# FPGA.net
KiCad netlist of a schematic drawn in Altium Designer
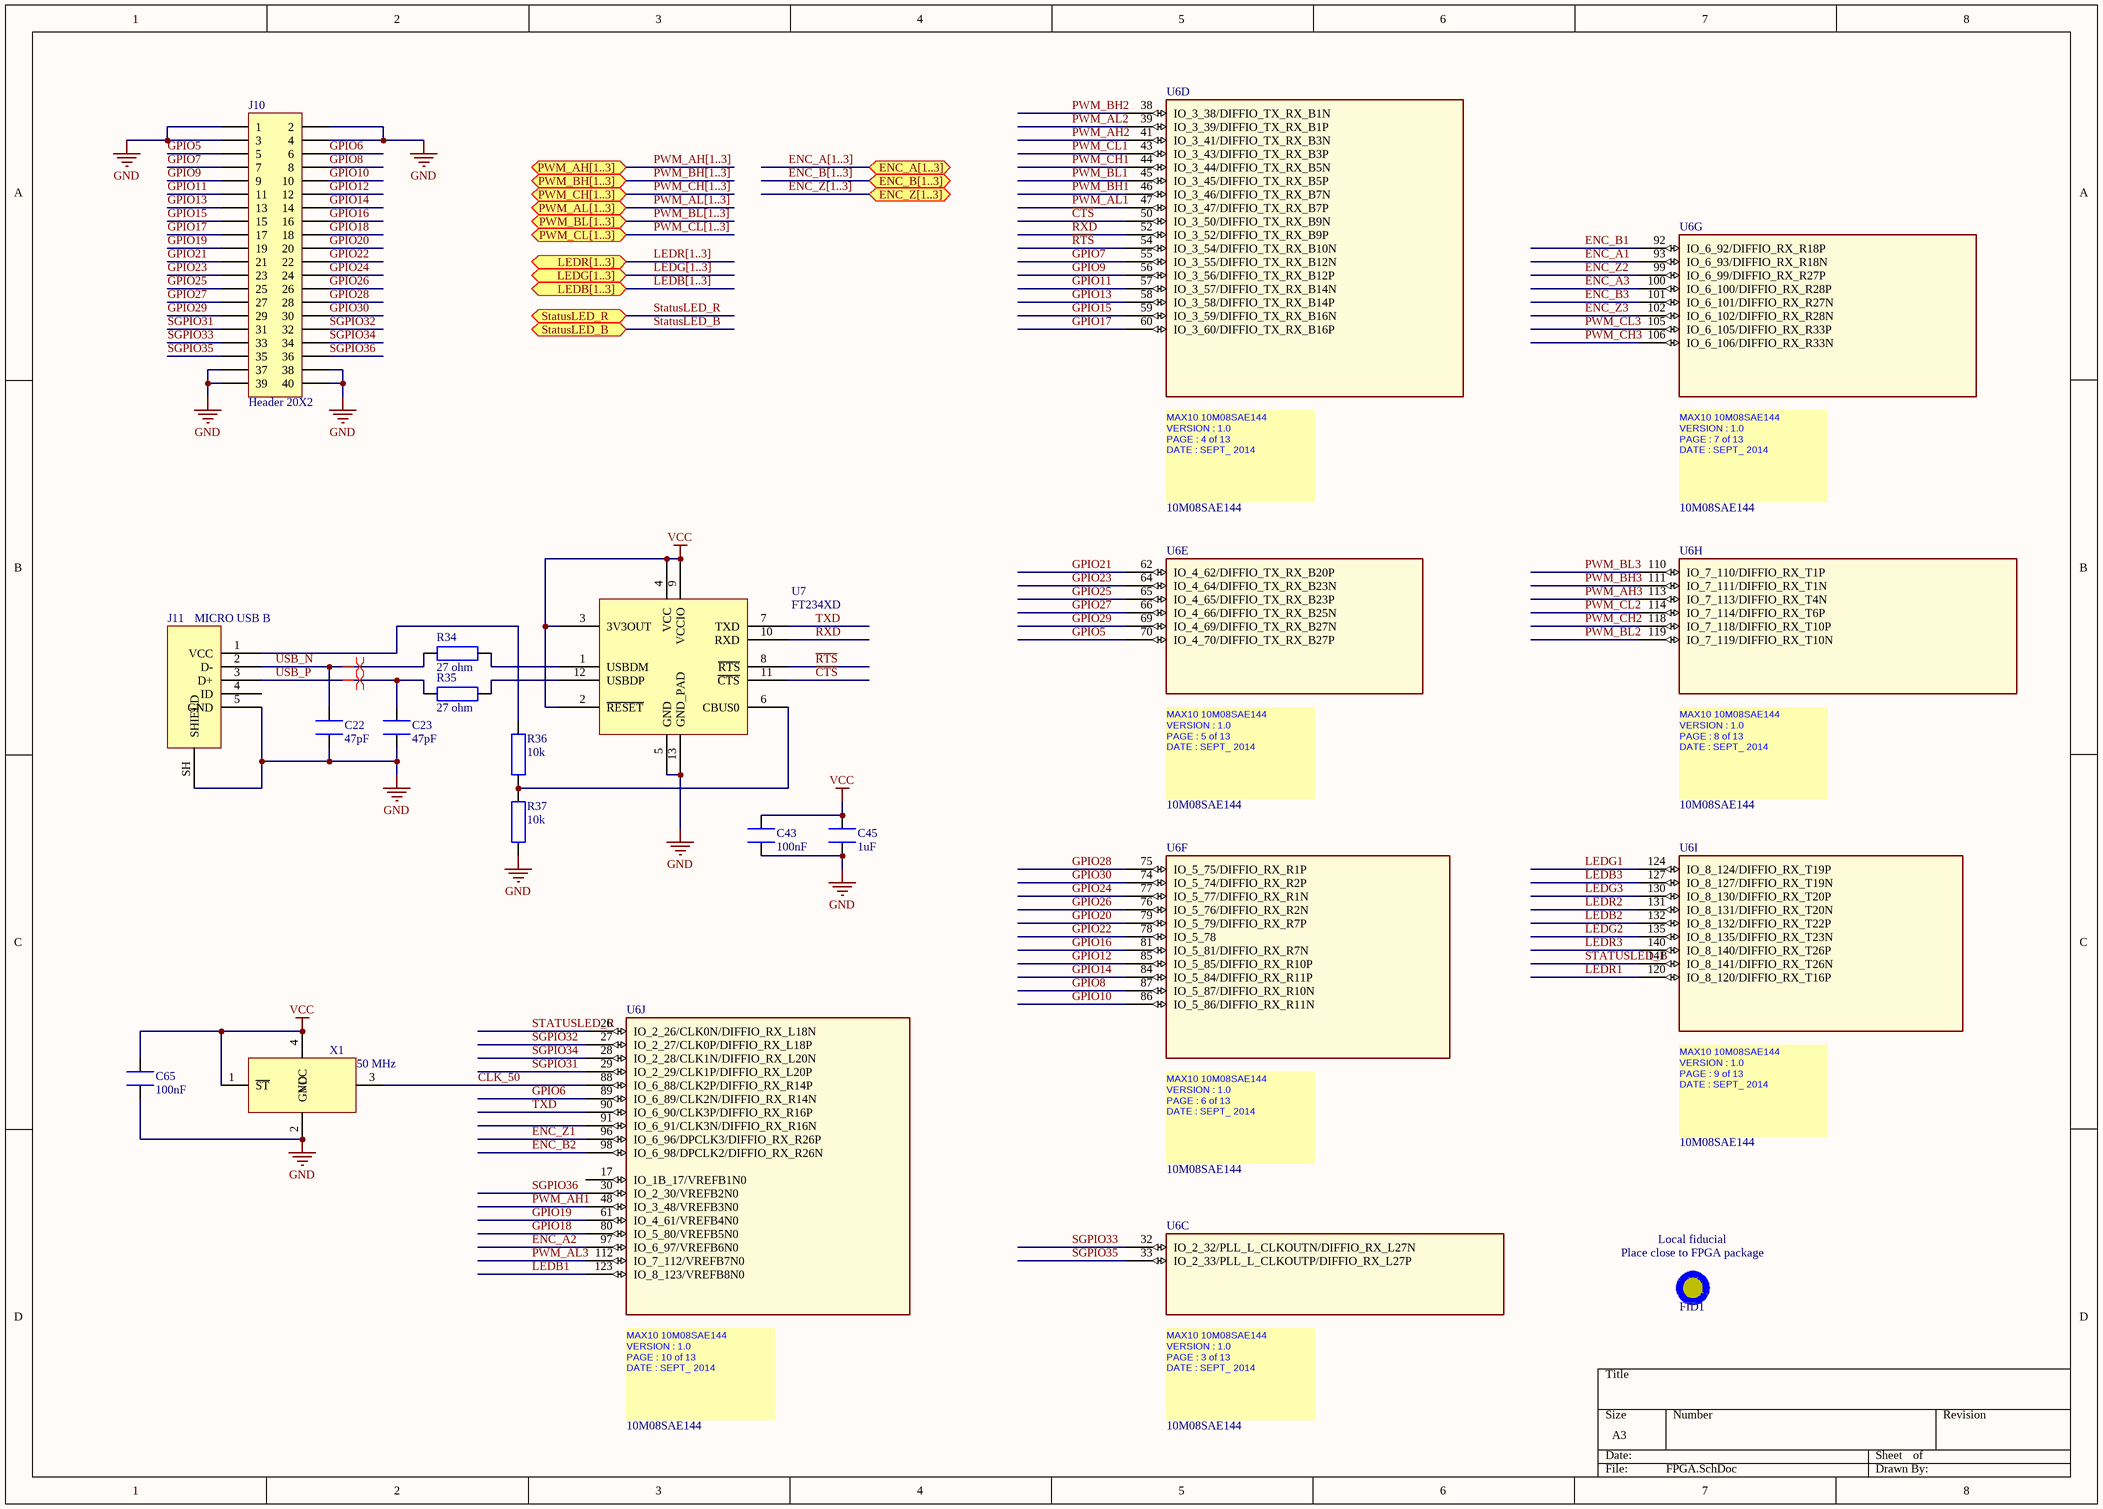
[diagram p0: FPGA.SchDoc]

(export (version "E")
  (design (tool "Eeschema 10.0.6"))
  (components
    (comp (ref "C22")
      (value "47pF")
      (footprint "1608[0603]")
      (description "CAP, MLCC, C0G/NP0, 47PF, 50V, 0603")
      (fields (field (name "Comment") "MC0603N470J500CT"))
      (libsource (lib "CustomComponents") (part "MC0603N470J500CT"))
    )
    (comp (ref "C23")
      (value "47pF")
      (footprint "1608[0603]")
      (description "CAP, MLCC, C0G/NP0, 47PF, 50V, 0603")
      (fields (field (name "Comment") "MC0603N470J500CT"))
      (libsource (lib "CustomComponents") (part "MC0603N470J500CT"))
    )
    (comp (ref "C43")
      (value "100nF")
      (footprint "1608[0603]")
      (description "CAP, MLCC, X7R, 100NF, 16V, 0603")
      (fields (field (name "Comment") "MC0603B104K160CT"))
      (libsource (lib "CustomComponents") (part "MC0603B104K160CT"))
    )
    (comp (ref "C45")
      (value "1uF")
      (footprint "1608[0603]")
      (description "CAP, MLCC, X5R, 1UF, 16V, 0603")
      (fields (field (name "Comment") "MC0603X105K160"))
      (libsource (lib "CustomComponents") (part "MC0603X105K160"))
    )
    (comp (ref "C65")
      (value "100nF")
      (footprint "1608[0603]")
      (description "CAP, MLCC, X7R, 100NF, 16V, 0603")
      (fields (field (name "Comment") "MC0603B104K160CT"))
      (libsource (lib "CustomComponents") (part "MC0603B104K160CT"))
    )
    (comp (ref "FID1")
      (value "FIDUCIAL")
      (footprint "FIDUCIAL")
      (description "1mm Fiducial with 2mm soldermask, 3mm keepout")
      (libsource (lib "CustomComponents") (part "FIDUCIAL"))
    )
    (comp (ref "J10")
      (value "Header 20X2")
      (footprint "HDR2X20")
      (description "Header, 20-Pin, Dual row")
      (fields (field (name "PUBLISHER") "Altium Limited"))
      (libsource (lib "Miscellaneous Connectors") (part "Header 20X2"))
    )
    (comp (ref "J11")
      (value "MICRO USB B")
      (footprint "USB_0103594-0001LF")
      (description "MICRO USB B, RECEPTACLE, SMT, RA, 5WAY")
      (libsource (lib "CustomComponents") (part "10103594-0001LF"))
    )
    (comp (ref "R34")
      (value "27 ohm")
      (footprint "RESC1608X55N")
      (description "RES, THICK FILM, 27OHM, 1%, 0.1W")
      (fields (field (name "Comment") "MCWR06X27R0FTL"))
      (libsource (lib "CustomComponents") (part "MCWR06X27R0FTL"))
    )
    (comp (ref "R35")
      (value "27 ohm")
      (footprint "RESC1608X55N")
      (description "RES, THICK FILM, 27OHM, 1%, 0.1W")
      (fields (field (name "Comment") "MCWR06X27R0FTL"))
      (libsource (lib "CustomComponents") (part "MCWR06X27R0FTL"))
    )
    (comp (ref "R36")
      (value "10k")
      (footprint "RESC1608X06L")
      (description "Resistor, 10k, 0603")
      (fields (field (name "Comment") "MCMR06X1002FTL"))
      (libsource (lib "CustomComponents") (part "MCMR06X1002FTL"))
    )
    (comp (ref "R37")
      (value "10k")
      (footprint "RESC1608X06L")
      (description "Resistor, 10k, 0603")
      (fields (field (name "Comment") "MCMR06X1002FTL"))
      (libsource (lib "CustomComponents") (part "MCMR06X1002FTL"))
    )
    (comp (ref "U6")
      (value "10M08SAE144")
      (footprint "SQFP50P2200X2200X165_HS-145N")
      (libsource (lib "10M08SAREVERSIONTEST_Library") (part "10M08SAE144"))
    )
    (comp (ref "U7")
      (value "FT234XD")
      (footprint "SON45P300X90_HS-13N")
      (libsource (lib "CustomComponents") (part "FT234XD"))
    )
    (comp (ref "X1")
      (value "50 MHz")
      (footprint "SPXO SG-210STF")
      (description "OSCILLATOR, SPXO, SG-210STF, 50 MHZ, SMD")
      (fields (field (name "Comment") "X1G0041710047"))
      (libsource (lib "CustomComponents") (part "X1G0041710047"))
    )
  )
  (nets
    (net (code "1") (name "/CLK_50") (class "Default")
      (node (ref "U6") (pin "88") (pinfunction "IO_6_88/CLK2P/DIFFIO_RX_R14P_88") (pintype "bidirectional"))
      (node (ref "X1") (pin "3") (pinfunction "CLKout_3") (pintype "passive"))
    )
    (net (code "2") (name "/CTS") (class "Default")
      (node (ref "U6") (pin "50") (pinfunction "IO_3_50/DIFFIO_TX_RX_B9N_50") (pintype "bidirectional"))
      (node (ref "U7") (pin "11") (pinfunction "CTS_11") (pintype "passive"))
    )
    (net (code "3") (name "/ENC_A1") (class "Default")
      (node (ref "U6") (pin "93") (pinfunction "IO_6_93/DIFFIO_RX_R18N_93") (pintype "bidirectional"))
    )
    (net (code "4") (name "/ENC_A2") (class "Default")
      (node (ref "U6") (pin "97") (pinfunction "IO_6_97/VREFB6N0_97") (pintype "bidirectional"))
    )
    (net (code "5") (name "/ENC_A3") (class "Default")
      (node (ref "U6") (pin "100") (pinfunction "IO_6_100/DIFFIO_RX_R28P_100") (pintype "bidirectional"))
    )
    (net (code "7") (name "/ENC_B1") (class "Default")
      (node (ref "U6") (pin "92") (pinfunction "IO_6_92/DIFFIO_RX_R18P_92") (pintype "bidirectional"))
    )
    (net (code "8") (name "/ENC_B2") (class "Default")
      (node (ref "U6") (pin "98") (pinfunction "IO_6_98/DPCLK2/DIFFIO_RX_R26N_98") (pintype "bidirectional"))
    )
    (net (code "9") (name "/ENC_B3") (class "Default")
      (node (ref "U6") (pin "101") (pinfunction "IO_6_101/DIFFIO_RX_R27N_101") (pintype "bidirectional"))
    )
    (net (code "11") (name "/ENC_Z1") (class "Default")
      (node (ref "U6") (pin "96") (pinfunction "IO_6_96/DPCLK3/DIFFIO_RX_R26P_96") (pintype "bidirectional"))
    )
    (net (code "12") (name "/ENC_Z2") (class "Default")
      (node (ref "U6") (pin "99") (pinfunction "IO_6_99/DIFFIO_RX_R27P_99") (pintype "bidirectional"))
    )
    (net (code "13") (name "/ENC_Z3") (class "Default")
      (node (ref "U6") (pin "102") (pinfunction "IO_6_102/DIFFIO_RX_R28N_102") (pintype "bidirectional"))
    )
    (net (code "15") (name "/GPIO5") (class "Default")
      (node (ref "J10") (pin "5") (pinfunction "5_5") (pintype "passive"))
      (node (ref "U6") (pin "70") (pinfunction "IO_4_70/DIFFIO_TX_RX_B27P_70") (pintype "bidirectional"))
    )
    (net (code "16") (name "/GPIO6") (class "Default")
      (node (ref "J10") (pin "6") (pinfunction "6_6") (pintype "passive"))
      (node (ref "U6") (pin "89") (pinfunction "IO_6_89/CLK2N/DIFFIO_RX_R14N_89") (pintype "bidirectional"))
    )
    (net (code "17") (name "/GPIO7") (class "Default")
      (node (ref "J10") (pin "7") (pinfunction "7_7") (pintype "passive"))
      (node (ref "U6") (pin "55") (pinfunction "IO_3_55/DIFFIO_TX_RX_B12N_55") (pintype "bidirectional"))
    )
    (net (code "18") (name "/GPIO8") (class "Default")
      (node (ref "J10") (pin "8") (pinfunction "8_8") (pintype "passive"))
      (node (ref "U6") (pin "87") (pinfunction "IO_5_87/DIFFIO_RX_R10N_87") (pintype "bidirectional"))
    )
    (net (code "19") (name "/GPIO9") (class "Default")
      (node (ref "J10") (pin "9") (pinfunction "9_9") (pintype "passive"))
      (node (ref "U6") (pin "56") (pinfunction "IO_3_56/DIFFIO_TX_RX_B12P_56") (pintype "bidirectional"))
    )
    (net (code "20") (name "/GPIO10") (class "Default")
      (node (ref "J10") (pin "10") (pinfunction "10_10") (pintype "passive"))
      (node (ref "U6") (pin "86") (pinfunction "IO_5_86/DIFFIO_RX_R11N_86") (pintype "bidirectional"))
    )
    (net (code "21") (name "/GPIO11") (class "Default")
      (node (ref "J10") (pin "11") (pinfunction "11_11") (pintype "passive"))
      (node (ref "U6") (pin "57") (pinfunction "IO_3_57/DIFFIO_TX_RX_B14N_57") (pintype "bidirectional"))
    )
    (net (code "22") (name "/GPIO12") (class "Default")
      (node (ref "J10") (pin "12") (pinfunction "12_12") (pintype "passive"))
      (node (ref "U6") (pin "85") (pinfunction "IO_5_85/DIFFIO_RX_R10P_85") (pintype "bidirectional"))
    )
    (net (code "23") (name "/GPIO13") (class "Default")
      (node (ref "J10") (pin "13") (pinfunction "13_13") (pintype "passive"))
      (node (ref "U6") (pin "58") (pinfunction "IO_3_58/DIFFIO_TX_RX_B14P_58") (pintype "bidirectional"))
    )
    (net (code "24") (name "/GPIO14") (class "Default")
      (node (ref "J10") (pin "14") (pinfunction "14_14") (pintype "passive"))
      (node (ref "U6") (pin "84") (pinfunction "IO_5_84/DIFFIO_RX_R11P_84") (pintype "bidirectional"))
    )
    (net (code "25") (name "/GPIO15") (class "Default")
      (node (ref "J10") (pin "15") (pinfunction "15_15") (pintype "passive"))
      (node (ref "U6") (pin "59") (pinfunction "IO_3_59/DIFFIO_TX_RX_B16N_59") (pintype "bidirectional"))
    )
    (net (code "26") (name "/GPIO16") (class "Default")
      (node (ref "J10") (pin "16") (pinfunction "16_16") (pintype "passive"))
      (node (ref "U6") (pin "81") (pinfunction "IO_5_81/DIFFIO_RX_R7N_81") (pintype "bidirectional"))
    )
    (net (code "27") (name "/GPIO17") (class "Default")
      (node (ref "J10") (pin "17") (pinfunction "17_17") (pintype "passive"))
      (node (ref "U6") (pin "60") (pinfunction "IO_3_60/DIFFIO_TX_RX_B16P_60") (pintype "bidirectional"))
    )
    (net (code "28") (name "/GPIO18") (class "Default")
      (node (ref "J10") (pin "18") (pinfunction "18_18") (pintype "passive"))
      (node (ref "U6") (pin "80") (pinfunction "IO_5_80/VREFB5N0_80") (pintype "bidirectional"))
    )
    (net (code "29") (name "/GPIO19") (class "Default")
      (node (ref "J10") (pin "19") (pinfunction "19_19") (pintype "passive"))
      (node (ref "U6") (pin "61") (pinfunction "IO_4_61/VREFB4N0_61") (pintype "bidirectional"))
    )
    (net (code "30") (name "/GPIO20") (class "Default")
      (node (ref "J10") (pin "20") (pinfunction "20_20") (pintype "passive"))
      (node (ref "U6") (pin "79") (pinfunction "IO_5_79/DIFFIO_RX_R7P_79") (pintype "bidirectional"))
    )
    (net (code "31") (name "/GPIO21") (class "Default")
      (node (ref "J10") (pin "21") (pinfunction "21_21") (pintype "passive"))
      (node (ref "U6") (pin "62") (pinfunction "IO_4_62/DIFFIO_TX_RX_B20P_62") (pintype "bidirectional"))
    )
    (net (code "32") (name "/GPIO22") (class "Default")
      (node (ref "J10") (pin "22") (pinfunction "22_22") (pintype "passive"))
      (node (ref "U6") (pin "78") (pinfunction "IO_5_78_78") (pintype "bidirectional"))
    )
    (net (code "33") (name "/GPIO23") (class "Default")
      (node (ref "J10") (pin "23") (pinfunction "23_23") (pintype "passive"))
      (node (ref "U6") (pin "64") (pinfunction "IO_4_64/DIFFIO_TX_RX_B23N_64") (pintype "bidirectional"))
    )
    (net (code "34") (name "/GPIO24") (class "Default")
      (node (ref "J10") (pin "24") (pinfunction "24_24") (pintype "passive"))
      (node (ref "U6") (pin "77") (pinfunction "IO_5_77/DIFFIO_RX_R1N_77") (pintype "bidirectional"))
    )
    (net (code "35") (name "/GPIO25") (class "Default")
      (node (ref "J10") (pin "25") (pinfunction "25_25") (pintype "passive"))
      (node (ref "U6") (pin "65") (pinfunction "IO_4_65/DIFFIO_TX_RX_B23P_65") (pintype "bidirectional"))
    )
    (net (code "36") (name "/GPIO26") (class "Default")
      (node (ref "J10") (pin "26") (pinfunction "26_26") (pintype "passive"))
      (node (ref "U6") (pin "76") (pinfunction "IO_5_76/DIFFIO_RX_R2N_76") (pintype "bidirectional"))
    )
    (net (code "37") (name "/GPIO27") (class "Default")
      (node (ref "J10") (pin "27") (pinfunction "27_27") (pintype "passive"))
      (node (ref "U6") (pin "66") (pinfunction "IO_4_66/DIFFIO_TX_RX_B25N_66") (pintype "bidirectional"))
    )
    (net (code "38") (name "/GPIO28") (class "Default")
      (node (ref "J10") (pin "28") (pinfunction "28_28") (pintype "passive"))
      (node (ref "U6") (pin "75") (pinfunction "IO_5_75/DIFFIO_RX_R1P_75") (pintype "bidirectional"))
    )
    (net (code "39") (name "/GPIO29") (class "Default")
      (node (ref "J10") (pin "29") (pinfunction "29_29") (pintype "passive"))
      (node (ref "U6") (pin "69") (pinfunction "IO_4_69/DIFFIO_TX_RX_B27N_69") (pintype "bidirectional"))
    )
    (net (code "40") (name "/GPIO30") (class "Default")
      (node (ref "J10") (pin "30") (pinfunction "30_30") (pintype "passive"))
      (node (ref "U6") (pin "74") (pinfunction "IO_5_74/DIFFIO_RX_R2P_74") (pintype "bidirectional"))
    )
    (net (code "41") (name "/LEDB1") (class "Default")
      (node (ref "U6") (pin "123") (pinfunction "IO_8_123/VREFB8N0_123") (pintype "bidirectional"))
    )
    (net (code "42") (name "/LEDB2") (class "Default")
      (node (ref "U6") (pin "132") (pinfunction "IO_8_132/DIFFIO_RX_T22P_132") (pintype "bidirectional"))
    )
    (net (code "43") (name "/LEDB3") (class "Default")
      (node (ref "U6") (pin "127") (pinfunction "IO_8_127/DIFFIO_RX_T19N_127") (pintype "bidirectional"))
    )
    (net (code "45") (name "/LEDG1") (class "Default")
      (node (ref "U6") (pin "124") (pinfunction "IO_8_124/DIFFIO_RX_T19P_124") (pintype "bidirectional"))
    )
    (net (code "46") (name "/LEDG2") (class "Default")
      (node (ref "U6") (pin "135") (pinfunction "IO_8_135/DIFFIO_RX_T23N_135") (pintype "bidirectional"))
    )
    (net (code "47") (name "/LEDG3") (class "Default")
      (node (ref "U6") (pin "130") (pinfunction "IO_8_130/DIFFIO_RX_T20P_130") (pintype "bidirectional"))
    )
    (net (code "49") (name "/LEDR1") (class "Default")
      (node (ref "U6") (pin "120") (pinfunction "IO_8_120/DIFFIO_RX_T16P_120") (pintype "bidirectional"))
    )
    (net (code "50") (name "/LEDR2") (class "Default")
      (node (ref "U6") (pin "131") (pinfunction "IO_8_131/DIFFIO_RX_T20N_131") (pintype "bidirectional"))
    )
    (net (code "51") (name "/LEDR3") (class "Default")
      (node (ref "U6") (pin "140") (pinfunction "IO_8_140/DIFFIO_RX_T26P_140") (pintype "bidirectional"))
    )
    (net (code "53") (name "/PWM_AH1") (class "Default")
      (node (ref "U6") (pin "48") (pinfunction "IO_3_48/VREFB3N0_48") (pintype "bidirectional"))
    )
    (net (code "54") (name "/PWM_AH2") (class "Default")
      (node (ref "U6") (pin "41") (pinfunction "IO_3_41/DIFFIO_TX_RX_B3N_41") (pintype "bidirectional"))
    )
    (net (code "55") (name "/PWM_AH3") (class "Default")
      (node (ref "U6") (pin "113") (pinfunction "IO_7_113/DIFFIO_RX_T4N_113") (pintype "bidirectional"))
    )
    (net (code "57") (name "/PWM_AL1") (class "Default")
      (node (ref "U6") (pin "47") (pinfunction "IO_3_47/DIFFIO_TX_RX_B7P_47") (pintype "bidirectional"))
    )
    (net (code "58") (name "/PWM_AL2") (class "Default")
      (node (ref "U6") (pin "39") (pinfunction "IO_3_39/DIFFIO_TX_RX_B1P_39") (pintype "bidirectional"))
    )
    (net (code "59") (name "/PWM_AL3") (class "Default")
      (node (ref "U6") (pin "112") (pinfunction "IO_7_112/VREFB7N0_112") (pintype "bidirectional"))
    )
    (net (code "61") (name "/PWM_BH1") (class "Default")
      (node (ref "U6") (pin "46") (pinfunction "IO_3_46/DIFFIO_TX_RX_B7N_46") (pintype "bidirectional"))
    )
    (net (code "62") (name "/PWM_BH2") (class "Default")
      (node (ref "U6") (pin "38") (pinfunction "IO_3_38/DIFFIO_TX_RX_B1N_38") (pintype "bidirectional"))
    )
    (net (code "63") (name "/PWM_BH3") (class "Default")
      (node (ref "U6") (pin "111") (pinfunction "IO_7_111/DIFFIO_RX_T1N_111") (pintype "bidirectional"))
    )
    (net (code "65") (name "/PWM_BL1") (class "Default")
      (node (ref "U6") (pin "45") (pinfunction "IO_3_45/DIFFIO_TX_RX_B5P_45") (pintype "bidirectional"))
    )
    (net (code "66") (name "/PWM_BL2") (class "Default")
      (node (ref "U6") (pin "119") (pinfunction "IO_7_119/DIFFIO_RX_T10N_119") (pintype "bidirectional"))
    )
    (net (code "67") (name "/PWM_BL3") (class "Default")
      (node (ref "U6") (pin "110") (pinfunction "IO_7_110/DIFFIO_RX_T1P_110") (pintype "bidirectional"))
    )
    (net (code "69") (name "/PWM_CH1") (class "Default")
      (node (ref "U6") (pin "44") (pinfunction "IO_3_44/DIFFIO_TX_RX_B5N_44") (pintype "bidirectional"))
    )
    (net (code "70") (name "/PWM_CH2") (class "Default")
      (node (ref "U6") (pin "118") (pinfunction "IO_7_118/DIFFIO_RX_T10P_118") (pintype "bidirectional"))
    )
    (net (code "71") (name "/PWM_CH3") (class "Default")
      (node (ref "U6") (pin "106") (pinfunction "IO_6_106/DIFFIO_RX_R33N_106") (pintype "bidirectional"))
    )
    (net (code "73") (name "/PWM_CL1") (class "Default")
      (node (ref "U6") (pin "43") (pinfunction "IO_3_43/DIFFIO_TX_RX_B3P_43") (pintype "bidirectional"))
    )
    (net (code "74") (name "/PWM_CL2") (class "Default")
      (node (ref "U6") (pin "114") (pinfunction "IO_7_114/DIFFIO_RX_T6P_114") (pintype "bidirectional"))
    )
    (net (code "75") (name "/PWM_CL3") (class "Default")
      (node (ref "U6") (pin "105") (pinfunction "IO_6_105/DIFFIO_RX_R33P_105") (pintype "bidirectional"))
    )
    (net (code "77") (name "/RTS") (class "Default")
      (node (ref "U6") (pin "54") (pinfunction "IO_3_54/DIFFIO_TX_RX_B10N_54") (pintype "bidirectional"))
      (node (ref "U7") (pin "8") (pinfunction "RTS_8") (pintype "passive"))
    )
    (net (code "78") (name "/RXD") (class "Default")
      (node (ref "U6") (pin "52") (pinfunction "IO_3_52/DIFFIO_TX_RX_B9P_52") (pintype "bidirectional"))
      (node (ref "U7") (pin "10") (pinfunction "RXD_10") (pintype "passive"))
    )
    (net (code "79") (name "/SGPIO31") (class "Default")
      (node (ref "J10") (pin "31") (pinfunction "31_31") (pintype "passive"))
      (node (ref "U6") (pin "29") (pinfunction "IO_2_29/CLK1P/DIFFIO_RX_L20P_29") (pintype "bidirectional"))
    )
    (net (code "80") (name "/SGPIO32") (class "Default")
      (node (ref "J10") (pin "32") (pinfunction "32_32") (pintype "passive"))
      (node (ref "U6") (pin "27") (pinfunction "IO_2_27/CLK0P/DIFFIO_RX_L18P_27") (pintype "bidirectional"))
    )
    (net (code "81") (name "/SGPIO33") (class "Default")
      (node (ref "J10") (pin "33") (pinfunction "33_33") (pintype "passive"))
      (node (ref "U6") (pin "32") (pinfunction "IO_2_32/PLL_L_CLKOUTN/DIFFIO_RX_L27N_32") (pintype "bidirectional"))
    )
    (net (code "82") (name "/SGPIO34") (class "Default")
      (node (ref "J10") (pin "34") (pinfunction "34_34") (pintype "passive"))
      (node (ref "U6") (pin "28") (pinfunction "IO_2_28/CLK1N/DIFFIO_RX_L20N_28") (pintype "bidirectional"))
    )
    (net (code "83") (name "/SGPIO35") (class "Default")
      (node (ref "J10") (pin "35") (pinfunction "35_35") (pintype "passive"))
      (node (ref "U6") (pin "33") (pinfunction "IO_2_33/PLL_L_CLKOUTP/DIFFIO_RX_L27P_33") (pintype "bidirectional"))
    )
    (net (code "84") (name "/SGPIO36") (class "Default")
      (node (ref "J10") (pin "36") (pinfunction "36_36") (pintype "passive"))
      (node (ref "U6") (pin "30") (pinfunction "IO_2_30/VREFB2N0_30") (pintype "bidirectional"))
    )
    (net (code "85") (name "/STATUSLED_B") (class "Default")
      (node (ref "U6") (pin "141") (pinfunction "IO_8_141/DIFFIO_RX_T26N_141") (pintype "bidirectional"))
    )
    (net (code "86") (name "/STATUSLED_R") (class "Default")
      (node (ref "U6") (pin "26") (pinfunction "IO_2_26/CLK0N/DIFFIO_RX_L18N_26") (pintype "bidirectional"))
    )
    (net (code "89") (name "/TXD") (class "Default")
      (node (ref "U6") (pin "90") (pinfunction "IO_6_90/CLK3P/DIFFIO_RX_R16P_90") (pintype "bidirectional"))
      (node (ref "U7") (pin "7") (pinfunction "TXD_7") (pintype "passive"))
    )
    (net (code "90") (name "/USB_N") (class "Default")
      (node (ref "C22") (pin "2") (pinfunction "2_2") (pintype "passive"))
      (node (ref "J11") (pin "2") (pinfunction "D-_2") (pintype "passive"))
      (node (ref "R34") (pin "2") (pinfunction "0_2") (pintype "passive"))
    )
    (net (code "91") (name "/USB_P") (class "Default")
      (node (ref "C23") (pin "2") (pinfunction "2_2") (pintype "passive"))
      (node (ref "J11") (pin "3") (pinfunction "D+_3") (pintype "passive"))
      (node (ref "R35") (pin "2") (pinfunction "0_2") (pintype "passive"))
    )
    (net (code "92") (name "GND") (class "Default")
      (node (ref "C22") (pin "1") (pinfunction "1_1") (pintype "passive"))
      (node (ref "C23") (pin "1") (pinfunction "1_1") (pintype "passive"))
      (node (ref "C43") (pin "1") (pinfunction "1_1") (pintype "passive"))
      (node (ref "C45") (pin "1") (pinfunction "1_1") (pintype "passive"))
      (node (ref "C65") (pin "1") (pinfunction "1_1") (pintype "passive"))
      (node (ref "J10") (pin "1") (pinfunction "1_1") (pintype "passive"))
      (node (ref "J10") (pin "2") (pinfunction "2_2") (pintype "passive"))
      (node (ref "J10") (pin "3") (pinfunction "3_3") (pintype "passive"))
      (node (ref "J10") (pin "37") (pinfunction "37_37") (pintype "passive"))
      (node (ref "J10") (pin "38") (pinfunction "38_38") (pintype "passive"))
      (node (ref "J10") (pin "39") (pinfunction "39_39") (pintype "passive"))
      (node (ref "J10") (pin "4") (pinfunction "4_4") (pintype "passive"))
      (node (ref "J10") (pin "40") (pinfunction "40_40") (pintype "passive"))
      (node (ref "J11") (pin "5") (pinfunction "GND_5") (pintype "passive"))
      (node (ref "J11") (pin "SH") (pinfunction "SHIELD_SH") (pintype "passive"))
      (node (ref "R37") (pin "1") (pinfunction "0_1") (pintype "passive"))
      (node (ref "U7") (pin "13") (pinfunction "GND_PAD_13") (pintype "passive"))
      (node (ref "U7") (pin "5") (pinfunction "GND_5") (pintype "passive"))
      (node (ref "X1") (pin "2") (pinfunction "GND_2") (pintype "passive"))
    )
    (net (code "93") (name "Net-(J11-VCC)") (class "Default")
      (node (ref "J11") (pin "1") (pinfunction "VCC_1") (pintype "passive"))
      (node (ref "R36") (pin "2") (pinfunction "0_2") (pintype "passive"))
    )
    (net (code "94") (name "Net-(U7-CBUS0)") (class "Default")
      (node (ref "R36") (pin "1") (pinfunction "0_1") (pintype "passive"))
      (node (ref "R37") (pin "2") (pinfunction "0_2") (pintype "passive"))
      (node (ref "U7") (pin "6") (pinfunction "CBUS0_6") (pintype "passive"))
    )
    (net (code "95") (name "Net-(U7-USBDM)") (class "Default")
      (node (ref "R34") (pin "1") (pinfunction "0_1") (pintype "passive"))
      (node (ref "U7") (pin "1") (pinfunction "USBDM_1") (pintype "passive"))
    )
    (net (code "96") (name "Net-(U7-USBDP)") (class "Default")
      (node (ref "R35") (pin "1") (pinfunction "0_1") (pintype "passive"))
      (node (ref "U7") (pin "12") (pinfunction "USBDP_12") (pintype "passive"))
    )
    (net (code "97") (name "VCC") (class "Default")
      (node (ref "C43") (pin "2") (pinfunction "2_2") (pintype "passive"))
      (node (ref "C45") (pin "2") (pinfunction "2_2") (pintype "passive"))
      (node (ref "C65") (pin "2") (pinfunction "2_2") (pintype "passive"))
      (node (ref "U7") (pin "2") (pinfunction "RESET_2") (pintype "passive"))
      (node (ref "U7") (pin "3") (pinfunction "3V3OUT_3") (pintype "passive"))
      (node (ref "U7") (pin "4") (pinfunction "VCC_4") (pintype "passive"))
      (node (ref "U7") (pin "9") (pinfunction "VCCIO_9") (pintype "passive"))
      (node (ref "X1") (pin "1") (pinfunction "~{ST}_1") (pintype "passive"))
      (node (ref "X1") (pin "4") (pinfunction "VCC_4") (pintype "passive"))
    )
    (net (code "98") (name "unconnected-(J11-ID-Pad4)") (class "Default")
      (node (ref "J11") (pin "4") (pinfunction "ID_4") (pintype "passive"))
    )
    (net (code "99") (name "unconnected-(U6J-IO_1B_17{slash}VREFB1N0-Pad17)") (class "Default")
      (node (ref "U6") (pin "17") (pinfunction "IO_1B_17/VREFB1N0_17") (pintype "bidirectional"))
    )
    (net (code "100") (name "unconnected-(U6J-IO_6_91{slash}CLK3N{slash}DIFFIO_RX_R16N-Pad91)") (class "Default")
      (node (ref "U6") (pin "91") (pinfunction "IO_6_91/CLK3N/DIFFIO_RX_R16N_91") (pintype "bidirectional"))
    )
  )
)
